# pogojig.net
KiCad netlist of a schematic drawn in EAGLE
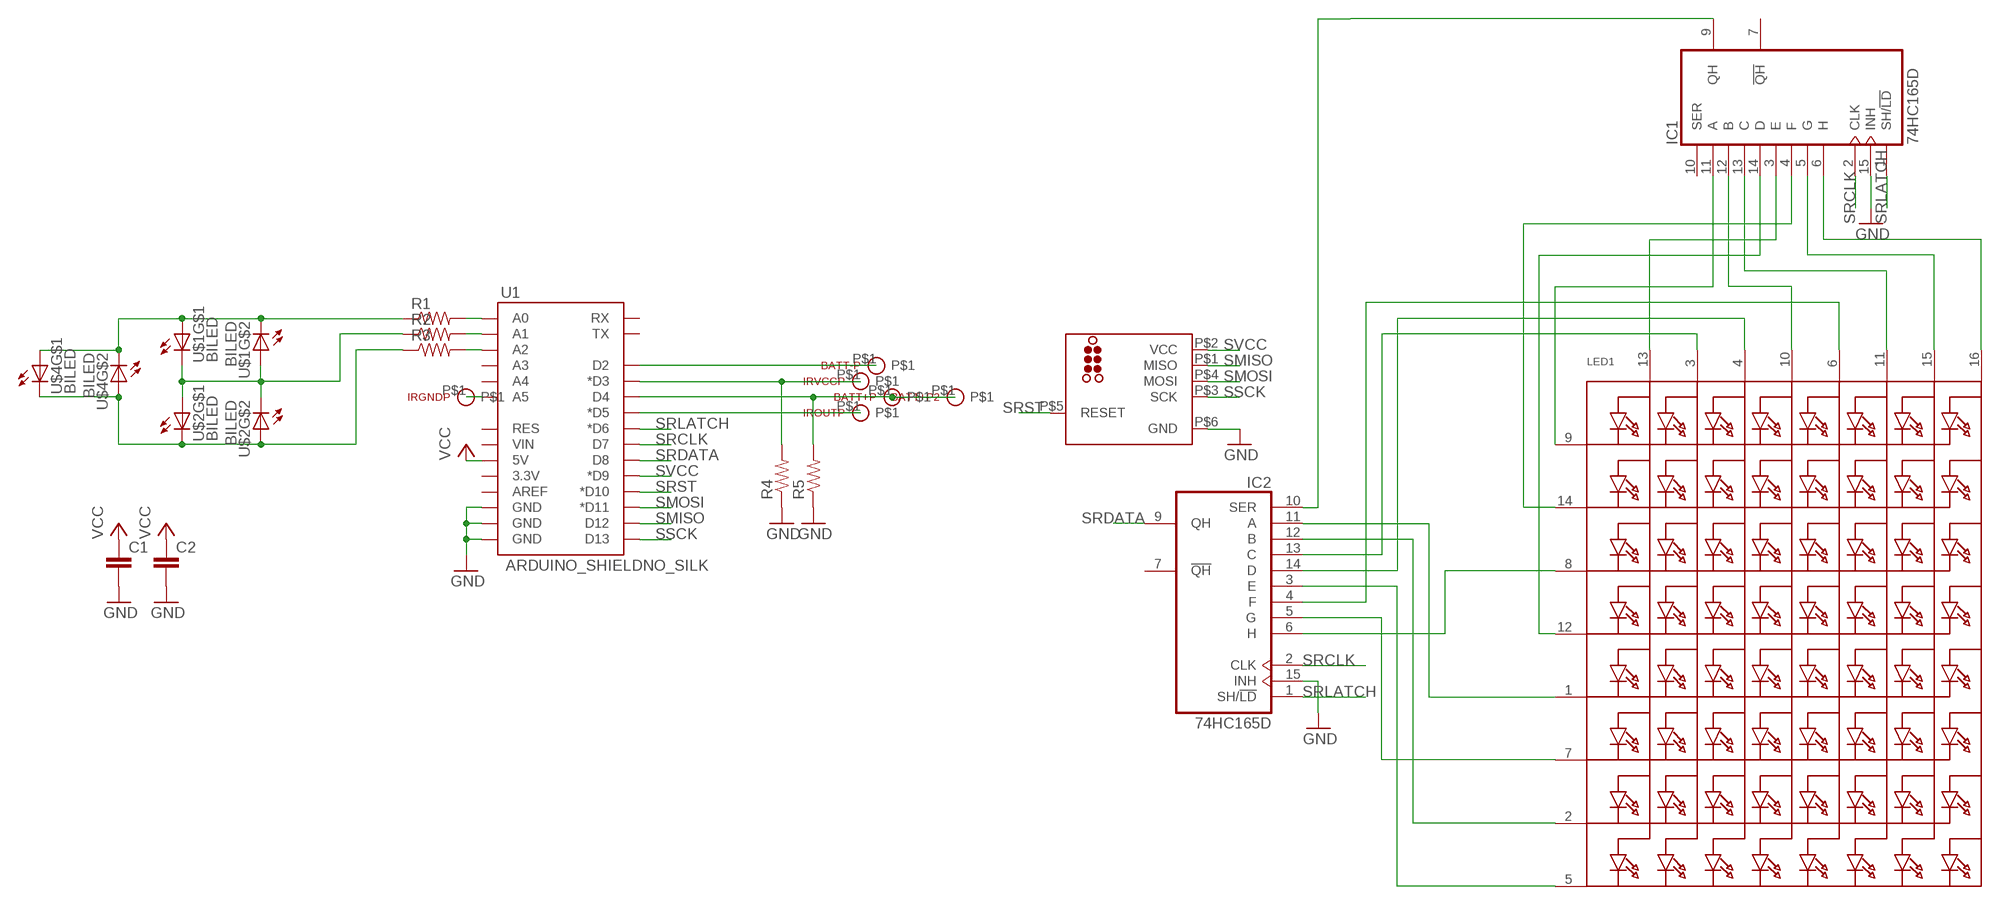
[diagram p0: schematic, sheet 1]

(export (version "E")
  (design (tool "Eeschema 10.0.6"))
  (components
    (comp (ref "BATT+P")
      (value "POGOPIN1.02")
      (footprint "eagle-import:POGOPIN-1.02")
      (libsource (lib "eagle-import") (part "POGOPIN1.02"))
    )
    (comp (ref "BATT+P2")
      (value "POGOPIN1.02")
      (footprint "eagle-import:POGOPIN-1.02")
      (libsource (lib "eagle-import") (part "POGOPIN1.02"))
    )
    (comp (ref "BATT-P")
      (value "POGOPIN1.02")
      (footprint "eagle-import:POGOPIN-1.02")
      (libsource (lib "eagle-import") (part "POGOPIN1.02"))
    )
    (comp (ref "C1")
      (value "CAP0805")
      (footprint "eagle-import:0805")
      (libsource (lib "eagle-import") (part "CAP0805"))
    )
    (comp (ref "C2")
      (value "CAP0805")
      (footprint "eagle-import:0805")
      (libsource (lib "eagle-import") (part "CAP0805"))
    )
    (comp (ref "IC1")
      (value "74HC165D")
      (footprint "eagle-import:SO16")
      (libsource (lib "eagle-import") (part "74165DHC"))
    )
    (comp (ref "IC2")
      (value "74HC165D")
      (footprint "eagle-import:SO16")
      (libsource (lib "eagle-import") (part "74165DHC"))
    )
    (comp (ref "IRGNDP")
      (value "POGOPIN1.02")
      (footprint "eagle-import:POGOPIN-1.02")
      (libsource (lib "eagle-import") (part "POGOPIN1.02"))
    )
    (comp (ref "IROUTP")
      (value "POGOPIN1.02")
      (footprint "eagle-import:POGOPIN-1.02")
      (libsource (lib "eagle-import") (part "POGOPIN1.02"))
    )
    (comp (ref "IRVCCP")
      (value "POGOPIN1.02")
      (footprint "eagle-import:POGOPIN-1.02")
      (libsource (lib "eagle-import") (part "POGOPIN1.02"))
    )
    (comp (ref "LED1")
      (value "SEGMENT_8X8_ROWCATHODE")
      (footprint "eagle-import:SEGMENT-30MM-POGO")
      (libsource (lib "eagle-import") (part "SEGMENT_8X8_ROWCATHODE"))
    )
    (comp (ref "R1")
      (value "RESISTOR0805-RES")
      (footprint "eagle-import:0805")
      (libsource (lib "eagle-import") (part "RESISTOR0805-RES"))
    )
    (comp (ref "R2")
      (value "RESISTOR0805-RES")
      (footprint "eagle-import:0805")
      (libsource (lib "eagle-import") (part "RESISTOR0805-RES"))
    )
    (comp (ref "R3")
      (value "RESISTOR0805-RES")
      (footprint "eagle-import:0805")
      (libsource (lib "eagle-import") (part "RESISTOR0805-RES"))
    )
    (comp (ref "R4")
      (value "RESISTOR0805-RES")
      (footprint "eagle-import:0805")
      (libsource (lib "eagle-import") (part "RESISTOR0805-RES"))
    )
    (comp (ref "R5")
      (value "RESISTOR0805-RES")
      (footprint "eagle-import:0805")
      (libsource (lib "eagle-import") (part "RESISTOR0805-RES"))
    )
    (comp (ref "U$1")
      (value "BILED")
      (footprint "eagle-import:BILED")
      (libsource (lib "eagle-import") (part "BILED"))
    )
    (comp (ref "U$2")
      (value "BILED")
      (footprint "eagle-import:BILED")
      (libsource (lib "eagle-import") (part "BILED"))
    )
    (comp (ref "U$3")
      (value "TC2030_AVR")
      (footprint "eagle-import:TC2030-MCP-NL-POGO")
      (libsource (lib "eagle-import") (part "TC2030_AVR"))
    )
    (comp (ref "U$4")
      (value "BILED")
      (footprint "eagle-import:BILED")
      (libsource (lib "eagle-import") (part "BILED"))
    )
    (comp (ref "U1")
      (value "ARDUINO_SHIELDNO_SILK")
      (footprint "eagle-import:DUEMILANOVE_VIAS")
      (libsource (lib "eagle-import") (part "ARDUINO_SHIELDNO_SILK"))
    )
  )
  (nets
    (net (code "1") (name "/SMISO") (class "Default")
      (node (ref "U$3") (pin "P$1") (pinfunction "MISO_P$1") (pintype "output"))
      (node (ref "U1") (pin "D12") (pinfunction "D12_D12") (pintype "bidirectional"))
    )
    (net (code "2") (name "/SMOSI") (class "Default")
      (node (ref "U$3") (pin "P$4") (pinfunction "MOSI_P$4") (pintype "input"))
      (node (ref "U1") (pin "D11") (pinfunction "*D11_D11") (pintype "bidirectional"))
    )
    (net (code "3") (name "/SRCLK") (class "Default")
      (node (ref "IC1") (pin "2") (pinfunction "CLK_2") (pintype "input"))
      (node (ref "IC2") (pin "2") (pinfunction "CLK_2") (pintype "input"))
      (node (ref "U1") (pin "D7") (pinfunction "D7_D7") (pintype "bidirectional"))
    )
    (net (code "4") (name "/SRDATA") (class "Default")
      (node (ref "IC2") (pin "9") (pinfunction "QH_9") (pintype "output"))
      (node (ref "U1") (pin "D8") (pinfunction "D8_D8") (pintype "bidirectional"))
    )
    (net (code "5") (name "/SRLATCH") (class "Default")
      (node (ref "IC1") (pin "1") (pinfunction "SH/~{LD}_1") (pintype "input"))
      (node (ref "IC2") (pin "1") (pinfunction "SH/~{LD}_1") (pintype "input"))
      (node (ref "U1") (pin "D6") (pinfunction "*D6_D6") (pintype "bidirectional"))
    )
    (net (code "6") (name "/SRST") (class "Default")
      (node (ref "U$3") (pin "P$5") (pinfunction "RESET_P$5") (pintype "output"))
      (node (ref "U1") (pin "D10") (pinfunction "*D10_D10") (pintype "bidirectional"))
    )
    (net (code "7") (name "/SSCK") (class "Default")
      (node (ref "U$3") (pin "P$3") (pinfunction "SCK_P$3") (pintype "output"))
      (node (ref "U1") (pin "D13") (pinfunction "D13_D13") (pintype "bidirectional"))
    )
    (net (code "8") (name "/SVCC") (class "Default")
      (node (ref "U$3") (pin "P$2") (pinfunction "VCC_P$2") (pintype "power_in"))
      (node (ref "U1") (pin "D9") (pinfunction "*D9_D9") (pintype "bidirectional"))
    )
    (net (code "9") (name "GND") (class "Default")
      (node (ref "C1") (pin "2") (pinfunction "2_2") (pintype "passive"))
      (node (ref "C2") (pin "2") (pinfunction "2_2") (pintype "passive"))
      (node (ref "IC1") (pin "15") (pinfunction "INH_15") (pintype "input"))
      (node (ref "IC2") (pin "15") (pinfunction "INH_15") (pintype "input"))
      (node (ref "R4") (pin "1") (pinfunction "1_1") (pintype "passive"))
      (node (ref "R5") (pin "1") (pinfunction "1_1") (pintype "passive"))
      (node (ref "U$3") (pin "P$6") (pinfunction "GND_P$6") (pintype "power_in"))
      (node (ref "U1") (pin "GND@0") (pinfunction "GND_GND@0") (pintype "bidirectional"))
      (node (ref "U1") (pin "GND@1") (pinfunction "GND_GND@1") (pintype "bidirectional"))
      (node (ref "U1") (pin "GND@2") (pinfunction "GND_GND@2") (pintype "bidirectional"))
    )
    (net (code "10") (name "Net-(BATT+P-PadP$1)") (class "Default")
      (node (ref "BATT+P") (pin "P$1") (pinfunction "P$1_P$1") (pintype "passive"))
      (node (ref "BATT+P2") (pin "P$1") (pinfunction "P$1_P$1") (pintype "passive"))
      (node (ref "R5") (pin "2") (pinfunction "2_2") (pintype "passive"))
      (node (ref "U1") (pin "D4") (pinfunction "D4_D4") (pintype "bidirectional"))
    )
    (net (code "11") (name "Net-(BATT-P-PadP$1)") (class "Default")
      (node (ref "BATT-P") (pin "P$1") (pinfunction "P$1_P$1") (pintype "passive"))
      (node (ref "U1") (pin "D2") (pinfunction "D2_D2") (pintype "bidirectional"))
    )
    (net (code "12") (name "Net-(IC1A-A)") (class "Default")
      (node (ref "IC1") (pin "11") (pinfunction "A_11") (pintype "input"))
      (node (ref "LED1") (pin "9") (pinfunction "K1_9") (pintype "bidirectional"))
    )
    (net (code "13") (name "Net-(IC1A-B)") (class "Default")
      (node (ref "IC1") (pin "12") (pinfunction "B_12") (pintype "input"))
      (node (ref "LED1") (pin "10") (pinfunction "A4_10") (pintype "bidirectional"))
    )
    (net (code "14") (name "Net-(IC1A-C)") (class "Default")
      (node (ref "IC1") (pin "13") (pinfunction "C_13") (pintype "input"))
      (node (ref "LED1") (pin "11") (pinfunction "A6_11") (pintype "bidirectional"))
    )
    (net (code "15") (name "Net-(IC1A-D)") (class "Default")
      (node (ref "IC1") (pin "14") (pinfunction "D_14") (pintype "input"))
      (node (ref "LED1") (pin "12") (pinfunction "K4_12") (pintype "bidirectional"))
    )
    (net (code "16") (name "Net-(IC1A-E)") (class "Default")
      (node (ref "IC1") (pin "3") (pinfunction "E_3") (pintype "input"))
      (node (ref "LED1") (pin "13") (pinfunction "A1_13") (pintype "bidirectional"))
    )
    (net (code "17") (name "Net-(IC1A-F)") (class "Default")
      (node (ref "IC1") (pin "4") (pinfunction "F_4") (pintype "input"))
      (node (ref "LED1") (pin "14") (pinfunction "K2_14") (pintype "bidirectional"))
    )
    (net (code "18") (name "Net-(IC1A-G)") (class "Default")
      (node (ref "IC1") (pin "5") (pinfunction "G_5") (pintype "input"))
      (node (ref "LED1") (pin "15") (pinfunction "A7_15") (pintype "bidirectional"))
    )
    (net (code "19") (name "Net-(IC1A-H)") (class "Default")
      (node (ref "IC1") (pin "6") (pinfunction "H_6") (pintype "input"))
      (node (ref "LED1") (pin "16") (pinfunction "A8_16") (pintype "bidirectional"))
    )
    (net (code "20") (name "Net-(IC1A-QH)") (class "Default")
      (node (ref "IC1") (pin "9") (pinfunction "QH_9") (pintype "output"))
      (node (ref "IC2") (pin "10") (pinfunction "SER_10") (pintype "input"))
    )
    (net (code "21") (name "Net-(IC2A-A)") (class "Default")
      (node (ref "IC2") (pin "11") (pinfunction "A_11") (pintype "input"))
      (node (ref "LED1") (pin "1") (pinfunction "K5_1") (pintype "bidirectional"))
    )
    (net (code "22") (name "Net-(IC2A-B)") (class "Default")
      (node (ref "IC2") (pin "12") (pinfunction "B_12") (pintype "input"))
      (node (ref "LED1") (pin "2") (pinfunction "K7_2") (pintype "bidirectional"))
    )
    (net (code "23") (name "Net-(IC2A-C)") (class "Default")
      (node (ref "IC2") (pin "13") (pinfunction "C_13") (pintype "input"))
      (node (ref "LED1") (pin "3") (pinfunction "A2_3") (pintype "bidirectional"))
    )
    (net (code "24") (name "Net-(IC2A-D)") (class "Default")
      (node (ref "IC2") (pin "14") (pinfunction "D_14") (pintype "input"))
      (node (ref "LED1") (pin "4") (pinfunction "A3_4") (pintype "bidirectional"))
    )
    (net (code "25") (name "Net-(IC2A-E)") (class "Default")
      (node (ref "IC2") (pin "3") (pinfunction "E_3") (pintype "input"))
      (node (ref "LED1") (pin "5") (pinfunction "K8_5") (pintype "bidirectional"))
    )
    (net (code "26") (name "Net-(IC2A-F)") (class "Default")
      (node (ref "IC2") (pin "4") (pinfunction "F_4") (pintype "input"))
      (node (ref "LED1") (pin "6") (pinfunction "A5_6") (pintype "bidirectional"))
    )
    (net (code "27") (name "Net-(IC2A-G)") (class "Default")
      (node (ref "IC2") (pin "5") (pinfunction "G_5") (pintype "input"))
      (node (ref "LED1") (pin "7") (pinfunction "K6_7") (pintype "bidirectional"))
    )
    (net (code "28") (name "Net-(IC2A-H)") (class "Default")
      (node (ref "IC2") (pin "6") (pinfunction "H_6") (pintype "input"))
      (node (ref "LED1") (pin "8") (pinfunction "K3_8") (pintype "bidirectional"))
    )
    (net (code "29") (name "Net-(IRGNDP-PadP$1)") (class "Default")
      (node (ref "IRGNDP") (pin "P$1") (pinfunction "P$1_P$1") (pintype "passive"))
      (node (ref "U1") (pin "A5") (pinfunction "A5_A5") (pintype "bidirectional"))
    )
    (net (code "30") (name "Net-(R1-Pad2)") (class "Default")
      (node (ref "R1") (pin "2") (pinfunction "2_2") (pintype "passive"))
      (node (ref "U1") (pin "A0") (pinfunction "A0_A0") (pintype "bidirectional"))
    )
    (net (code "31") (name "Net-(R2-Pad2)") (class "Default")
      (node (ref "R2") (pin "2") (pinfunction "2_2") (pintype "passive"))
      (node (ref "U1") (pin "A1") (pinfunction "A1_A1") (pintype "bidirectional"))
    )
    (net (code "32") (name "Net-(R3-Pad2)") (class "Default")
      (node (ref "R3") (pin "2") (pinfunction "2_2") (pintype "passive"))
      (node (ref "U1") (pin "A2") (pinfunction "A2_A2") (pintype "bidirectional"))
    )
    (net (code "33") (name "Net-(U$1A-A)") (class "Default")
      (node (ref "R1") (pin "1") (pinfunction "1_1") (pintype "passive"))
      (node (ref "U$1") (pin "A1") (pinfunction "A_A1") (pintype "passive"))
      (node (ref "U$1") (pin "C2") (pinfunction "C_C2") (pintype "passive"))
      (node (ref "U$4") (pin "A1") (pinfunction "A_A1") (pintype "passive"))
      (node (ref "U$4") (pin "C2") (pinfunction "C_C2") (pintype "passive"))
    )
    (net (code "34") (name "Net-(U$1A-C)") (class "Default")
      (node (ref "R2") (pin "1") (pinfunction "1_1") (pintype "passive"))
      (node (ref "U$1") (pin "A2") (pinfunction "A_A2") (pintype "passive"))
      (node (ref "U$1") (pin "C1") (pinfunction "C_C1") (pintype "passive"))
      (node (ref "U$2") (pin "A1") (pinfunction "A_A1") (pintype "passive"))
      (node (ref "U$2") (pin "C2") (pinfunction "C_C2") (pintype "passive"))
    )
    (net (code "35") (name "Net-(U$2A-C)") (class "Default")
      (node (ref "R3") (pin "1") (pinfunction "1_1") (pintype "passive"))
      (node (ref "U$2") (pin "A2") (pinfunction "A_A2") (pintype "passive"))
      (node (ref "U$2") (pin "C1") (pinfunction "C_C1") (pintype "passive"))
      (node (ref "U$4") (pin "A2") (pinfunction "A_A2") (pintype "passive"))
      (node (ref "U$4") (pin "C1") (pinfunction "C_C1") (pintype "passive"))
    )
    (net (code "36") (name "Net-(U1-*D3)") (class "Default")
      (node (ref "IRVCCP") (pin "P$1") (pinfunction "P$1_P$1") (pintype "passive"))
      (node (ref "R4") (pin "2") (pinfunction "2_2") (pintype "passive"))
      (node (ref "U1") (pin "D3") (pinfunction "*D3_D3") (pintype "bidirectional"))
    )
    (net (code "37") (name "Net-(U1-*D5)") (class "Default")
      (node (ref "IROUTP") (pin "P$1") (pinfunction "P$1_P$1") (pintype "passive"))
      (node (ref "U1") (pin "D5") (pinfunction "*D5_D5") (pintype "bidirectional"))
    )
    (net (code "38") (name "VCC") (class "Default")
      (node (ref "C1") (pin "1") (pinfunction "1_1") (pintype "passive"))
      (node (ref "C2") (pin "1") (pinfunction "1_1") (pintype "passive"))
      (node (ref "U1") (pin "5V") (pinfunction "5V_5V") (pintype "bidirectional"))
    )
    (net (code "39") (name "unconnected-(IC1A-SER-Pad10)") (class "Default")
      (node (ref "IC1") (pin "10") (pinfunction "SER_10") (pintype "input"))
    )
    (net (code "40") (name "unconnected-(IC1A-~{QH}-Pad7)") (class "Default")
      (node (ref "IC1") (pin "7") (pinfunction "~{QH}_7") (pintype "output"))
    )
    (net (code "41") (name "unconnected-(IC2A-~{QH}-Pad7)") (class "Default")
      (node (ref "IC2") (pin "7") (pinfunction "~{QH}_7") (pintype "output"))
    )
    (net (code "42") (name "unconnected-(U1-Pad3.3V)") (class "Default")
      (node (ref "U1") (pin "3.3V") (pinfunction "3.3V_3.3V") (pintype "bidirectional"))
    )
    (net (code "43") (name "unconnected-(U1-PadA3)") (class "Default")
      (node (ref "U1") (pin "A3") (pinfunction "A3_A3") (pintype "bidirectional"))
    )
    (net (code "44") (name "unconnected-(U1-PadA4)") (class "Default")
      (node (ref "U1") (pin "A4") (pinfunction "A4_A4") (pintype "bidirectional"))
    )
    (net (code "45") (name "unconnected-(U1-PadAREF)") (class "Default")
      (node (ref "U1") (pin "AREF") (pinfunction "AREF_AREF") (pintype "bidirectional"))
    )
    (net (code "46") (name "unconnected-(U1-PadRES)") (class "Default")
      (node (ref "U1") (pin "RES") (pinfunction "RES_RES") (pintype "bidirectional"))
    )
    (net (code "47") (name "unconnected-(U1-PadRX)") (class "Default")
      (node (ref "U1") (pin "RX") (pinfunction "RX_RX") (pintype "bidirectional"))
    )
    (net (code "48") (name "unconnected-(U1-PadTX)") (class "Default")
      (node (ref "U1") (pin "TX") (pinfunction "TX_TX") (pintype "bidirectional"))
    )
    (net (code "49") (name "unconnected-(U1-PadVIN)") (class "Default")
      (node (ref "U1") (pin "VIN") (pinfunction "VIN_VIN") (pintype "bidirectional"))
    )
  )
)
